# Mynd_BT.net
KiCad netlist of a schematic drawn in Altium Designer
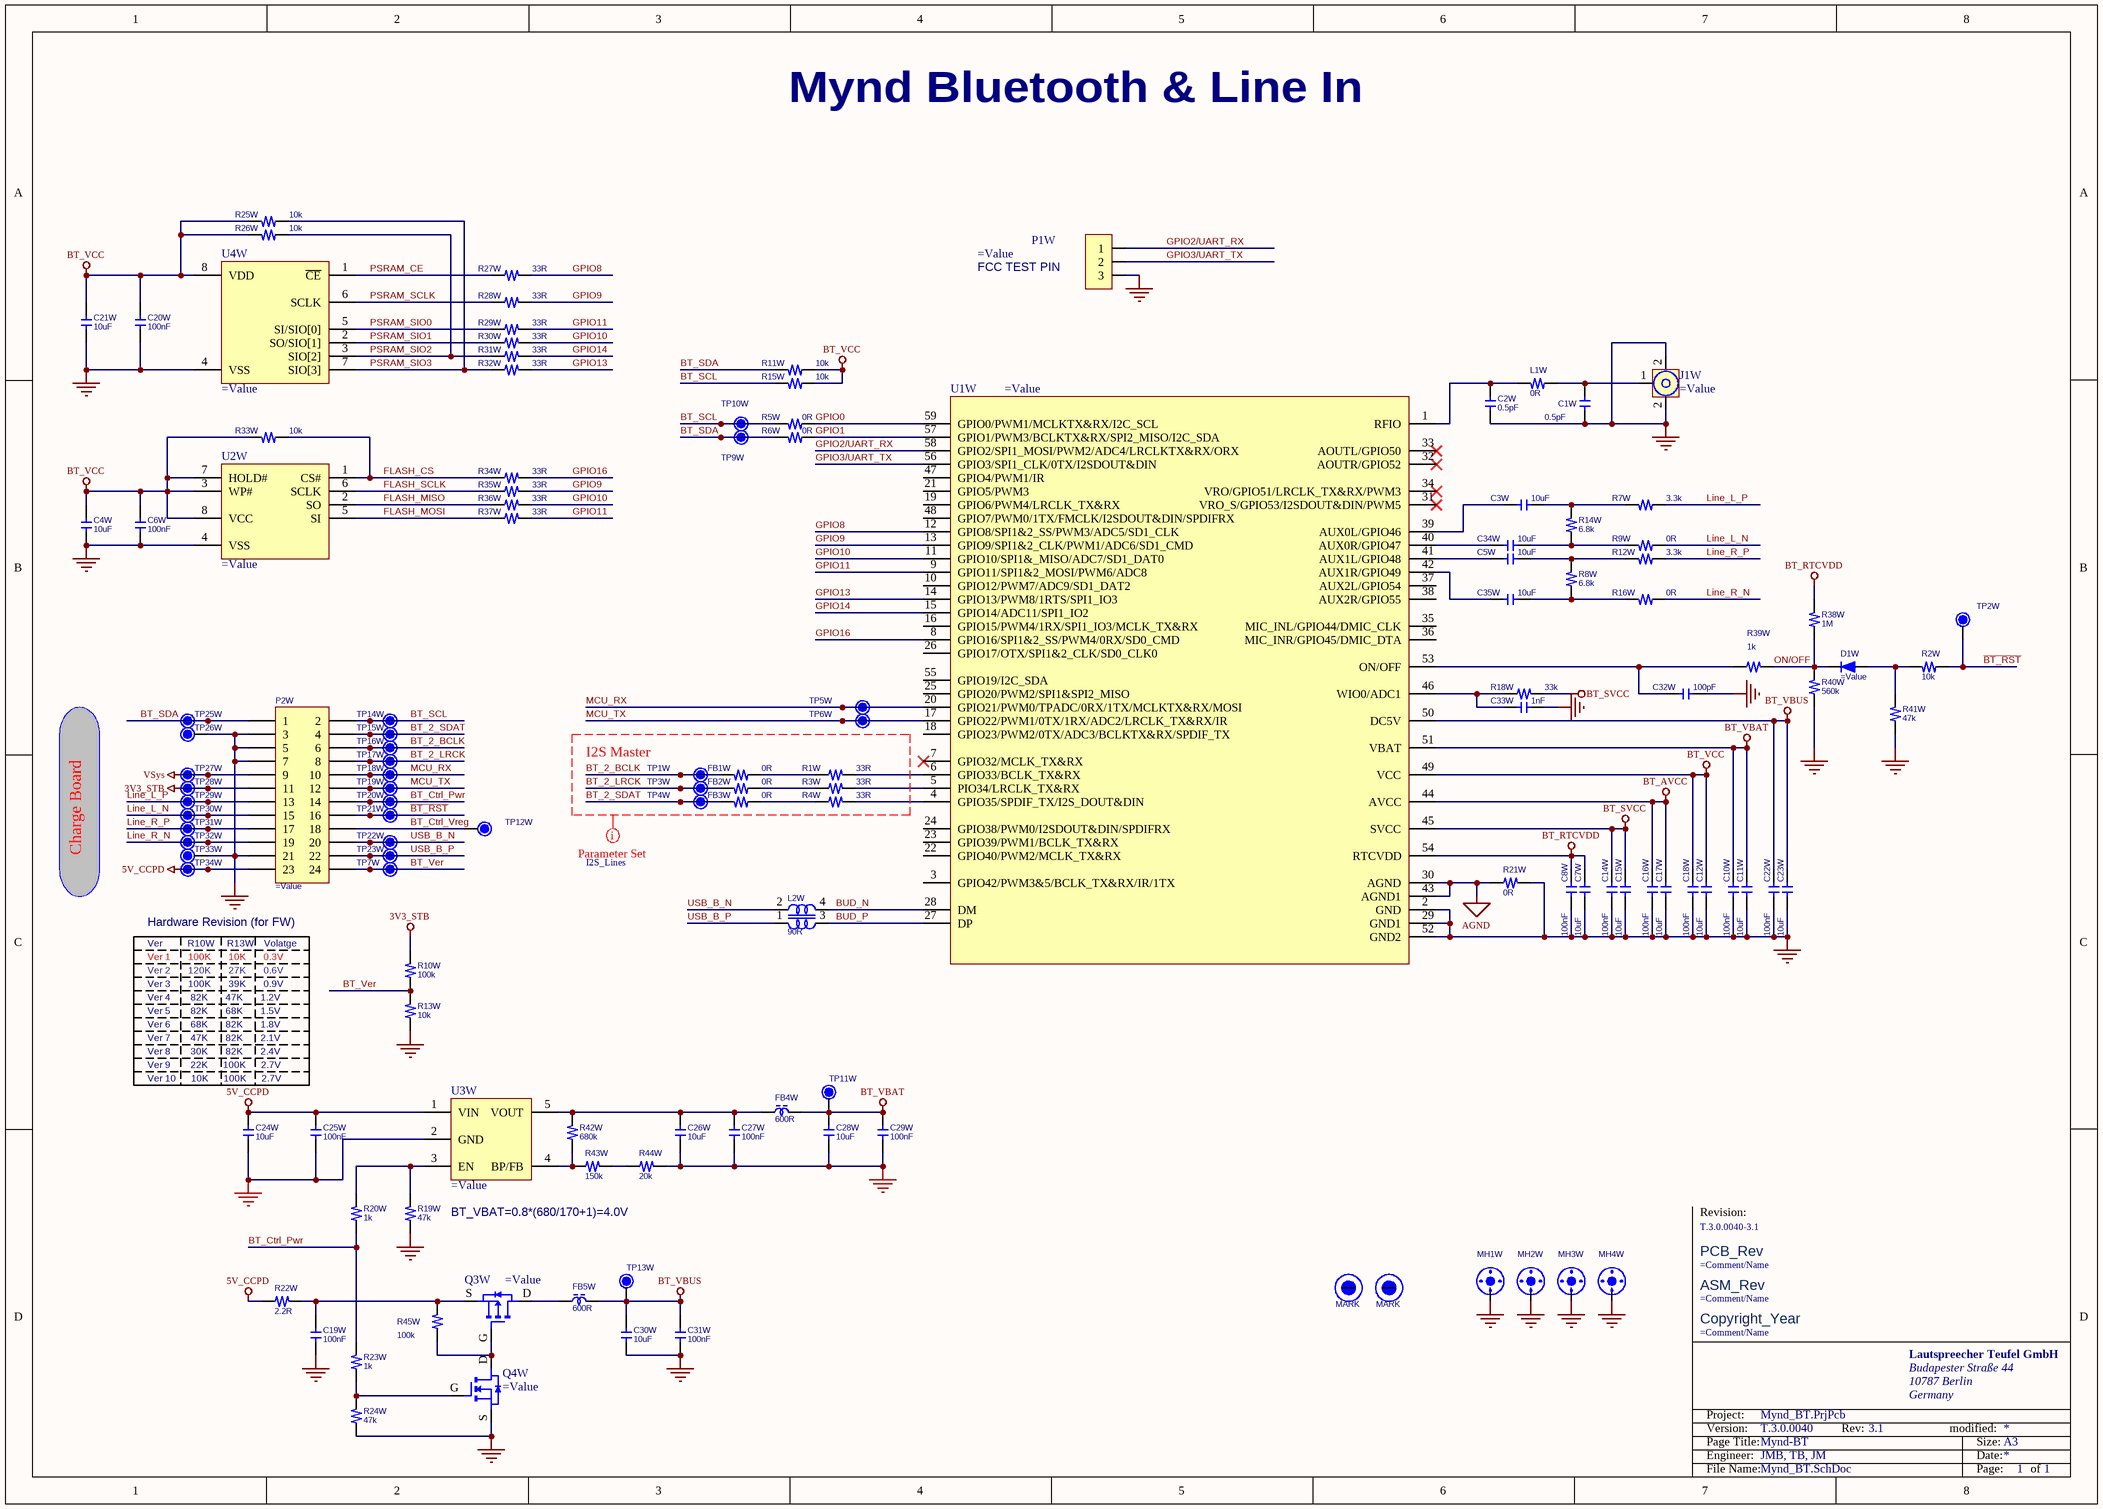
[diagram p0: Mynd_BT.SchDoc]

(export (version "E")
  (design (tool "Eeschema 10.0.6"))
  (components
    (comp (ref "C1W")
      (value "0.5pF")
      (footprint "C0402")
      (description "GP SMD M CAP 0.5pF 50V ±0.1pF 0402 NPO")
      (fields (field (name "MANUFACTURER") "Multi Sourced") (field (name "TOLERANCE") "±0.1pF"))
      (libsource (lib "altium-import") (part "root_3_mirrored_CAP1_"))
    )
    (comp (ref "C2W")
      (value "0.5pF")
      (footprint "C0402")
      (description "GP SMD M CAP 0.5pF 50V ±0.1pF 0402 NPO")
      (fields (field (name "MANUFACTURER") "Multi Sourced") (field (name "TOLERANCE") "±0.1pF"))
      (libsource (lib "altium-import") (part "root_3_mirrored_CAP1_"))
    )
    (comp (ref "C3W")
      (value "10uF")
      (footprint "C0805_145")
      (description "PSHF SMD M CAP 10uF 16V ±10% 0805 X7R")
      (fields (field (name "MANUFACTURER") "Multi Sourced") (field (name "TOLERANCE") "±10% 0805"))
      (libsource (lib "altium-import") (part "root_0_CAP1_"))
    )
    (comp (ref "C4W")
      (value "10uF")
      (footprint "C0805_145")
      (description "PSHF SMD M CAP 10uF 16V ±10% 0805 X7R")
      (fields (field (name "MANUFACTURER") "Multi Sourced") (field (name "TOLERANCE") "±10% 0805"))
      (libsource (lib "altium-import") (part "root_1_P-001-0158-27_"))
    )
    (comp (ref "C5W")
      (value "10uF")
      (footprint "C0805_145")
      (description "PSHF SMD M CAP 10uF 16V ±10% 0805 X7R")
      (fields (field (name "MANUFACTURER") "Multi Sourced") (field (name "TOLERANCE") "±10% 0805"))
      (libsource (lib "altium-import") (part "root_0_CAP1_"))
    )
    (comp (ref "C6W")
      (value "100nF")
      (footprint "C0603X100")
      (description "PSHF SMD M CAP 100nF 16V ±10%  0603 X7R")
      (fields (field (name "MANUFACTURER") "Multi Sourced") (field (name "TOLERANCE") "±10%"))
      (libsource (lib "altium-import") (part "root_1_CAP1_"))
    )
    (comp (ref "C7W")
      (value "10uF")
      (footprint "C0805_145")
      (description "PSHF SMD M CAP 10uF 16V ±10% 0805 X7R")
      (fields (field (name "MANUFACTURER") "Multi Sourced") (field (name "TOLERANCE") "±10% 0805"))
      (libsource (lib "altium-import") (part "root_3_CAP1_"))
    )
    (comp (ref "C8W")
      (value "100nF")
      (footprint "C0603X100")
      (description "PSHF SMD M CAP 100nF 16V ±10%  0603 X7R")
      (fields (field (name "MANUFACTURER") "Multi Sourced") (field (name "TOLERANCE") "±10%"))
      (libsource (lib "altium-import") (part "root_3_CAP1_"))
    )
    (comp (ref "C10W")
      (value "100nF")
      (footprint "C0603X100")
      (description "PSHF SMD M CAP 100nF 16V ±10%  0603 X7R")
      (fields (field (name "MANUFACTURER") "Multi Sourced") (field (name "TOLERANCE") "±10%"))
      (libsource (lib "altium-import") (part "root_1_CAP1_"))
    )
    (comp (ref "C11W")
      (value "10uF")
      (footprint "C0805_145")
      (description "PSHF SMD M CAP 10uF 16V ±10% 0805 X7R")
      (fields (field (name "MANUFACTURER") "Multi Sourced") (field (name "TOLERANCE") "±10% 0805"))
      (libsource (lib "altium-import") (part "root_1_P-001-0158-27_"))
    )
    (comp (ref "C12W")
      (value "10uF")
      (footprint "C0805_145")
      (description "PSHF SMD M CAP 10uF 16V ±10% 0805 X7R")
      (fields (field (name "MANUFACTURER") "Multi Sourced") (field (name "TOLERANCE") "±10% 0805"))
      (libsource (lib "altium-import") (part "root_1_CAP1_"))
    )
    (comp (ref "C14W")
      (value "100nF")
      (footprint "C0603X100")
      (description "PSHF SMD M CAP 100nF 16V ±10%  0603 X7R")
      (fields (field (name "MANUFACTURER") "Multi Sourced") (field (name "TOLERANCE") "±10%"))
      (libsource (lib "altium-import") (part "root_3_CAP1_"))
    )
    (comp (ref "C15W")
      (value "10uF")
      (footprint "C0805_145")
      (description "PSHF SMD M CAP 10uF 16V ±10% 0805 X7R")
      (fields (field (name "MANUFACTURER") "Multi Sourced") (field (name "TOLERANCE") "±10% 0805"))
      (libsource (lib "altium-import") (part "root_1_CAP1_"))
    )
    (comp (ref "C16W")
      (value "100nF")
      (footprint "C0603X100")
      (description "PSHF SMD M CAP 100nF 16V ±10%  0603 X7R")
      (fields (field (name "MANUFACTURER") "Multi Sourced") (field (name "TOLERANCE") "±10%"))
      (libsource (lib "altium-import") (part "root_3_CAP1_"))
    )
    (comp (ref "C17W")
      (value "10uF")
      (footprint "C0805_145")
      (description "PSHF SMD M CAP 10uF 16V ±10% 0805 X7R")
      (fields (field (name "MANUFACTURER") "Multi Sourced") (field (name "TOLERANCE") "±10% 0805"))
      (libsource (lib "altium-import") (part "root_1_CAP1_"))
    )
    (comp (ref "C18W")
      (value "100nF")
      (footprint "C0603X100")
      (description "PSHF SMD M CAP 100nF 16V ±10%  0603 X7R")
      (fields (field (name "MANUFACTURER") "Multi Sourced") (field (name "TOLERANCE") "±10%"))
      (libsource (lib "altium-import") (part "root_1_CAP1_"))
    )
    (comp (ref "C19W")
      (value "100nF")
      (footprint "C0603X100")
      (description "PSHF SMD M CAP 100nF 16V ±10%  0603 X7R")
      (fields (field (name "MANUFACTURER") "Multi Sourced") (field (name "TOLERANCE") "±10%"))
      (libsource (lib "altium-import") (part "root_3_CAP1_"))
    )
    (comp (ref "C20W")
      (value "100nF")
      (footprint "C0603X100")
      (description "PSHF SMD M CAP 100nF 16V ±10%  0603 X7R")
      (fields (field (name "MANUFACTURER") "Multi Sourced") (field (name "TOLERANCE") "±10%"))
      (libsource (lib "altium-import") (part "root_3_CAP1_"))
    )
    (comp (ref "C21W")
      (value "10uF")
      (footprint "C0805_145")
      (description "PSHF SMD M CAP 10uF 16V ±10% 0805 X7R")
      (fields (field (name "MANUFACTURER") "Multi Sourced") (field (name "TOLERANCE") "±10% 0805"))
      (libsource (lib "altium-import") (part "root_3_P-001-0158-27_"))
    )
    (comp (ref "C22W")
      (value "100nF")
      (footprint "C0603X100")
      (description "PSHF SMD M CAP 100nF 16V ±10%  0603 X7R")
      (fields (field (name "MANUFACTURER") "Multi Sourced") (field (name "TOLERANCE") "±10%"))
      (libsource (lib "altium-import") (part "root_3_P-001-0038-26_"))
    )
    (comp (ref "C23W")
      (value "10uF")
      (footprint "C0805_145")
      (description "PSHF SMD M CAP 10uF 16V ±10% 0805 X7R")
      (fields (field (name "MANUFACTURER") "Multi Sourced") (field (name "TOLERANCE") "±10% 0805"))
      (libsource (lib "altium-import") (part "root_3_CAP1_"))
    )
    (comp (ref "C24W")
      (value "10uF")
      (footprint "C0805_145")
      (description "PSHF SMD M CAP 10uF 16V ±10% 0805 0805 X5R")
      (fields (field (name "TOLERANCE") "±10% 0805") (field (name "MANUFACTURER") "Multi Sourced"))
      (libsource (lib "altium-import") (part "root_3_CAP1_"))
    )
    (comp (ref "C25W")
      (value "100nF")
      (footprint "C0603X100")
      (description "PSHF SMD M CAP 100nF 50V ±10% 0603 X7R")
      (fields (field (name "MANUFACTURER") "Multi Sourced") (field (name "PART_NUMBER") "Generic"))
      (libsource (lib "altium-import") (part "root_1_CAP1_"))
    )
    (comp (ref "C26W")
      (value "10uF")
      (footprint "C0805_145")
      (description "PSHF SMD M CAP 10uF 16V ±10% 0805 0805 X5R")
      (fields (field (name "TOLERANCE") "±10% 0805") (field (name "MANUFACTURER") "Multi Sourced"))
      (libsource (lib "altium-import") (part "root_3_CAP1_"))
    )
    (comp (ref "C27W")
      (value "100nF")
      (footprint "C0603X100")
      (description "PSHF SMD M CAP 100nF 16V ±10%  0603 X7R")
      (fields (field (name "MANUFACTURER") "Multi Sourced") (field (name "PART_NUMBER") "Generic"))
      (libsource (lib "altium-import") (part "root_1_CAP1_"))
    )
    (comp (ref "C28W")
      (value "10uF")
      (footprint "C0805_145")
      (description "PSHF SMD M CAP 10uF 16V ±10% 0805 0805 X5R")
      (fields (field (name "TOLERANCE") "±10% 0805") (field (name "MANUFACTURER") "Multi Sourced"))
      (libsource (lib "altium-import") (part "root_3_CAP1_"))
    )
    (comp (ref "C29W")
      (value "100nF")
      (footprint "C0603X100")
      (description "PSHF SMD M CAP 100nF 16V ±10%  0603 X7R")
      (fields (field (name "MANUFACTURER") "Multi Sourced") (field (name "PART_NUMBER") "Generic"))
      (libsource (lib "altium-import") (part "root_1_CAP1_"))
    )
    (comp (ref "C30W")
      (value "10uF")
      (footprint "C0805_145")
      (description "PSHF SMD M CAP 10uF 16V ±10% 0805 X7R")
      (fields (field (name "MANUFACTURER") "Multi Sourced") (field (name "TOLERANCE") "±10% 0805"))
      (libsource (lib "altium-import") (part "root_1_P-001-0158-27_"))
    )
    (comp (ref "C31W")
      (value "100nF")
      (footprint "C0603X100")
      (description "PSHF SMD M CAP 100nF 16V ±10%  0603 X7R")
      (fields (field (name "MANUFACTURER") "Multi Sourced") (field (name "TOLERANCE") "±10%"))
      (libsource (lib "altium-import") (part "root_1_CAP1_"))
    )
    (comp (ref "C32W")
      (value "100pF")
      (footprint "C0603X80")
      (description "PSHF SMD M CAP 100pF 50V ±10% 0603 X7R")
      (fields (field (name "MANUFACTURER") "Multi Sourced") (field (name "PART_NUMBER") "Generic"))
      (libsource (lib "altium-import") (part "root_2_CAP1_"))
    )
    (comp (ref "C33W")
      (value "1nF")
      (footprint "C0603X100")
      (description "PSHF SMD M CAP 1nF 50V ±10% 0603 X7R")
      (fields (field (name "MANUFACTURER") "Multi Sourced") (field (name "PART_NUMBER") "Generic"))
      (libsource (lib "altium-import") (part "root_2_CAP1_"))
    )
    (comp (ref "C34W")
      (value "10uF")
      (footprint "C0805_145")
      (description "PSHF SMD M CAP 10uF 16V ±10% 0805 X7R")
      (fields (field (name "MANUFACTURER") "Multi Sourced") (field (name "TOLERANCE") "±10% 0805"))
      (libsource (lib "altium-import") (part "root_0_CAP1_"))
    )
    (comp (ref "C35W")
      (value "10uF")
      (footprint "C0805_145")
      (description "PSHF SMD M CAP 10uF 16V ±10% 0805 X7R")
      (fields (field (name "MANUFACTURER") "Multi Sourced") (field (name "TOLERANCE") "±10% 0805"))
      (libsource (lib "altium-import") (part "root_0_CAP1_"))
    )
    (comp (ref "D1W")
      (value "~")
      (footprint "SOD-323")
      (description "PS SMD DIODE 2P 100V SOD323 1N4148 CJ")
      (fields (field (name "MANUFACTURER") "[CJ]") (field (name "PART_NUMBER") "1N4148"))
      (libsource (lib "altium-import") (part "root_2_DIODE_SWITCHING1_"))
    )
    (comp (ref "FB1W")
      (value "0R")
      (footprint "R0603")
      (description "GPHF SMD RES. 0OHM 1/10W 5% 0603")
      (fields (field (name "MANUFACTURER") "Multi Sourced") (field (name "TOLERANCE") "5%"))
      (libsource (lib "altium-import") (part "root_0_RES1_"))
    )
    (comp (ref "FB2W")
      (value "0R")
      (footprint "R0603")
      (description "GPHF SMD RES. 0OHM 1/10W 5% 0603")
      (fields (field (name "MANUFACTURER") "Multi Sourced") (field (name "TOLERANCE") "5%"))
      (libsource (lib "altium-import") (part "root_0_RES1_"))
    )
    (comp (ref "FB3W")
      (value "0R")
      (footprint "R0603")
      (description "GPHF SMD RES. 0OHM 1/10W 5% 0603")
      (fields (field (name "MANUFACTURER") "Multi Sourced") (field (name "TOLERANCE") "5%"))
      (libsource (lib "altium-import") (part "root_0_RES1_"))
    )
    (comp (ref "FB4W")
      (value "600R")
      (footprint "L0603")
      (description "PS SMD FERRITE BEAD 600OHM 25% 0603")
      (fields (field (name "MANUFACTURER") "[TSA]") (field (name "TOLERANCE") "1:25%"))
      (libsource (lib "altium-import") (part "root_0_Bead1_"))
    )
    (comp (ref "FB5W")
      (value "600R")
      (footprint "L0603")
      (description "PS SMD FERRITE BEAD 600OHM 25% 0603")
      (fields (field (name "MANUFACTURER") "[TSA]") (field (name "TOLERANCE") "1:25%"))
      (libsource (lib "altium-import") (part "root_0_Bead1_"))
    )
    (comp (ref "J1W")
      (value "~")
      (footprint "I-PEX MHF")
      (description "SMD ANTENNA JACK 2P FEMALE")
      (fields (field (name "MANUFACTURER") "[SONGCHENG]") (field (name "PART_NUMBER") "9181-000030"))
      (libsource (lib "altium-import") (part "root_2_COA_CON1_"))
    )
    (comp (ref "L1W")
      (value "0R")
      (footprint "R0402")
      (description "GPHF SMD RES. 0OHM 1/16W 5% 0402")
      (fields (field (name "MANUFACTURER") "Multi Sourced") (field (name "TOLERANCE") "5%"))
      (libsource (lib "altium-import") (part "root_0_mirrored_RES1_"))
    )
    (comp (ref "L2W")
      (value "90R")
      (footprint "COM_CHOKE_SMD_ICMF062P")
      (description "FILTER ICMF062P900MFR 100MHz 4P 90ohm")
      (fields (field (name "MANUFACTURER") "TSA") (field (name "PART_NUMBER") "ICMF062P900MFR"))
      (libsource (lib "altium-import") (part "root_2_mirrored_INDUCTOR_CM_4_"))
    )
    (comp (ref "MH1W")
      (value "SCREW_HOLE")
      (footprint "SCREW_D32")
      (description "SCREW_HOLE D3.2mm")
      (libsource (lib "altium-import") (part "root_1_SCREW_HOLE_"))
    )
    (comp (ref "MH2W")
      (value "SCREW_HOLE")
      (footprint "SCREW_D32")
      (description "SCREW_HOLE D3.2mm")
      (libsource (lib "altium-import") (part "root_1_SCREW_HOLE_"))
    )
    (comp (ref "MH3W")
      (value "SCREW_HOLE")
      (footprint "SCREW_D32")
      (description "SCREW_HOLE D3.2mm")
      (libsource (lib "altium-import") (part "root_1_SCREW_HOLE_"))
    )
    (comp (ref "MH4W")
      (value "SCREW_HOLE")
      (footprint "SCREW_D32")
      (description "SCREW_HOLE D3.2mm")
      (libsource (lib "altium-import") (part "root_1_SCREW_HOLE_"))
    )
    (comp (ref "MK1W")
      (value "MARK")
      (footprint "MARK")
      (description "MARK DOT")
      (libsource (lib "altium-import") (part "root_0_MARK_"))
    )
    (comp (ref "MK2W")
      (value "MARK")
      (footprint "MARK")
      (description "MARK DOT")
      (libsource (lib "altium-import") (part "root_0_MARK_"))
    )
    (comp (ref "P1W")
      (value "~")
      (footprint "Pin_Header_SMD_S_T_254_3P")
      (description "GP HEADER PIN 3P P=2.54mm 90° GOLD")
      (fields (field (name "PART_NUMBER") "Header 3P PITCH=2.54mm SMT"))
      (libsource (lib "altium-import") (part "root_0_CON 3P_"))
    )
    (comp (ref "P2W")
      (value "~")
      (footprint "Pin_Header_SMD_2X12_254")
      (description "SMD BTB CONNECTOR 24P P2.54mm GOLD")
      (fields
        (field (name "MANUFACTURER") "MINGHENG")
        (field (name "PART_NUMBER") "Connector 2 x 12P 2.54mm SMT")
      )
      (libsource (lib "altium-import") (part "root_0_CON 2x12P_"))
    )
    (comp (ref "Q3W")
      (value "~")
      (footprint "SOT23-GSD")
      (description "GS SMD FET 3P -30V SOT-23 CJ3401 CJ")
      (fields (field (name "MANUFACTURER") "[CJ]") (field (name "PART_NUMBER") "CJ3401"))
      (libsource (lib "altium-import") (part "root_1_mirrored_P-MOS1_"))
    )
    (comp (ref "Q4W")
      (value "~")
      (footprint "SOT23-GSD")
      (description "GP SMD FET 3P SOT23 2N7002K CTE")
      (fields (field (name "MANUFACTURER") "CTE") (field (name "PART_NUMBER") "2N7002K"))
      (libsource (lib "altium-import") (part "root_0_N-MOS1_"))
    )
    (comp (ref "R1W")
      (value "33R")
      (footprint "R0603")
      (description "PS SMD RES. 33OHM 1/10W 5% 0603")
      (fields (field (name "TOLERANCE") "5%") (field (name "MANUFACTURER") "Multi Sourced"))
      (libsource (lib "altium-import") (part "root_2_RES1_"))
    )
    (comp (ref "R2W")
      (value "10k")
      (footprint "R0603")
      (description "PS SMD RES. 10KOHM 1/10W 1% 0603")
      (fields (field (name "TOLERANCE") "1%") (field (name "MANUFACTURER") "Multi Sourced"))
      (libsource (lib "altium-import") (part "root_0_RES1_"))
    )
    (comp (ref "R3W")
      (value "33R")
      (footprint "R0603")
      (description "PS SMD RES. 33OHM 1/10W 5% 0603")
      (fields (field (name "TOLERANCE") "5%") (field (name "MANUFACTURER") "Multi Sourced"))
      (libsource (lib "altium-import") (part "root_2_RES1_"))
    )
    (comp (ref "R4W")
      (value "33R")
      (footprint "R0603")
      (description "PS SMD RES. 33OHM 1/10W 5% 0603")
      (fields (field (name "TOLERANCE") "5%") (field (name "MANUFACTURER") "Multi Sourced"))
      (libsource (lib "altium-import") (part "root_2_RES1_"))
    )
    (comp (ref "R5W")
      (value "0R")
      (footprint "R0603")
      (description "PS SMD RES. 0OHM 1/10W 5% 0603")
      (fields (field (name "TOLERANCE") "5%") (field (name "MANUFACTURER") "Multi Sourced"))
      (libsource (lib "altium-import") (part "root_0_RES1_"))
    )
    (comp (ref "R6W")
      (value "0R")
      (footprint "R0603")
      (description "PS SMD RES. 0OHM 1/10W 5% 0603")
      (fields (field (name "TOLERANCE") "5%") (field (name "MANUFACTURER") "Multi Sourced"))
      (libsource (lib "altium-import") (part "root_0_RES1_"))
    )
    (comp (ref "R7W")
      (value "3.3k")
      (footprint "R0603")
      (description "GPHF SMD RES. 3.3KOHM 1/10W 1% 0603")
      (fields (field (name "TOLERANCE") "1%") (field (name "MANUFACTURER") "Multi Sourced"))
      (libsource (lib "altium-import") (part "root_0_RES1_"))
    )
    (comp (ref "R8W")
      (value "6.8k")
      (footprint "R0603")
      (description "PS SMD RES. 6.8KOHM 1/10W 1% 0603")
      (fields (field (name "TOLERANCE") "1%") (field (name "MANUFACTURER") "Multi Sourced"))
      (libsource (lib "altium-import") (part "root_1_mirrored_RES1_"))
    )
    (comp (ref "R9W")
      (value "0R")
      (footprint "R0603")
      (description "PS SMD RES. 0OHM 1/10W 5% 0603")
      (fields (field (name "TOLERANCE") "5%") (field (name "MANUFACTURER") "Multi Sourced"))
      (libsource (lib "altium-import") (part "root_0_RES1_"))
    )
    (comp (ref "R10W")
      (value "100k")
      (footprint "R0603")
      (description "GPHF SMD RES. 100KOHM 1/10W 1% 0603")
      (fields (field (name "TOLERANCE") "1%") (field (name "MANUFACTURER") "Multi Sourced"))
      (libsource (lib "altium-import") (part "root_3_RES1_"))
    )
    (comp (ref "R11W")
      (value "10k")
      (footprint "R0603")
      (description "PS SMD RES. 10KOHM 1/10W 1% 0603")
      (fields (field (name "TOLERANCE") "1%") (field (name "MANUFACTURER") "Multi Sourced"))
      (libsource (lib "altium-import") (part "root_0_mirrored_RES1_"))
    )
    (comp (ref "R12W")
      (value "3.3k")
      (footprint "R0603")
      (description "GPHF SMD RES. 3.3KOHM 1/10W 1% 0603")
      (fields (field (name "TOLERANCE") "1%") (field (name "MANUFACTURER") "Multi Sourced"))
      (libsource (lib "altium-import") (part "root_0_RES1_"))
    )
    (comp (ref "R13W")
      (value "10k")
      (footprint "R0603")
      (description "GPHF SMD RES. 10KOHM 1/10W 1% 0603")
      (fields (field (name "TOLERANCE") "1%") (field (name "MANUFACTURER") "Multi Sourced"))
      (libsource (lib "altium-import") (part "root_3_RES1_"))
    )
    (comp (ref "R14W")
      (value "6.8k")
      (footprint "R0603")
      (description "PS SMD RES. 6.8KOHM 1/10W 1% 0603")
      (fields (field (name "TOLERANCE") "1%") (field (name "MANUFACTURER") "Multi Sourced"))
      (libsource (lib "altium-import") (part "root_1_mirrored_RES1_"))
    )
    (comp (ref "R15W")
      (value "10k")
      (footprint "R0603")
      (description "PS SMD RES. 10KOHM 1/10W 1% 0603")
      (fields (field (name "TOLERANCE") "1%") (field (name "MANUFACTURER") "Multi Sourced"))
      (libsource (lib "altium-import") (part "root_0_mirrored_RES1_"))
    )
    (comp (ref "R16W")
      (value "0R")
      (footprint "R0603")
      (description "PS SMD RES. 0OHM 1/10W 5% 0603")
      (fields (field (name "TOLERANCE") "5%") (field (name "MANUFACTURER") "Multi Sourced"))
      (libsource (lib "altium-import") (part "root_0_RES1_"))
    )
    (comp (ref "R18W")
      (value "33k")
      (footprint "R0603")
      (description "PS SMD RES. 33KOHM 1/10W 1% 0603")
      (fields (field (name "TOLERANCE") "1%") (field (name "MANUFACTURER") "Multi Sourced"))
      (libsource (lib "altium-import") (part "root_2_RES1_"))
    )
    (comp (ref "R19W")
      (value "47k")
      (footprint "R0603")
      (description "PS SMD RES. 47KOHM 1/10W 1% 0603")
      (fields (field (name "TOLERANCE") "1%") (field (name "MANUFACTURER") "Multi Sourced"))
      (libsource (lib "altium-import") (part "root_3_RES1_"))
    )
    (comp (ref "R20W")
      (value "1k")
      (footprint "R0603")
      (description "PS SMD RES. 1KOHM 1/10W 1% 0603")
      (fields (field (name "TOLERANCE") "1%") (field (name "MANUFACTURER") "Multi Sourced"))
      (libsource (lib "altium-import") (part "root_3_RES1_"))
    )
    (comp (ref "R21W")
      (value "0R")
      (footprint "R0603")
      (description "PS SMD RES. 0OHM 1/10W 5% 0603")
      (fields (field (name "TOLERANCE") "5%") (field (name "MANUFACTURER") "Multi Sourced"))
      (libsource (lib "altium-import") (part "root_2_RES1_"))
    )
    (comp (ref "R22W")
      (value "2.2R")
      (footprint "R0805")
      (description "PS SMD RES. 2.2OHM 1/8W 5% 0805")
      (fields (field (name "TOLERANCE") "5%") (field (name "MANUFACTURER") "Multi Sourced"))
      (libsource (lib "altium-import") (part "root_2_RES1_"))
    )
    (comp (ref "R23W")
      (value "1k")
      (footprint "R0603")
      (description "PS SMD RES. 1KOHM 1/10W 1% 0603")
      (fields (field (name "TOLERANCE") "1%") (field (name "MANUFACTURER") "Multi Sourced"))
      (libsource (lib "altium-import") (part "root_3_RES1_"))
    )
    (comp (ref "R24W")
      (value "47k")
      (footprint "R0603")
      (description "PS SMD RES. 47KOHM 1/10W 1% 0603")
      (fields (field (name "TOLERANCE") "1%") (field (name "MANUFACTURER") "Multi Sourced"))
      (libsource (lib "altium-import") (part "root_3_RES1_"))
    )
    (comp (ref "R25W")
      (value "10k")
      (footprint "R0603")
      (description "PS SMD RES. 10KOHM 1/10W 1% 0603")
      (fields (field (name "TOLERANCE") "1%") (field (name "MANUFACTURER") "Multi Sourced"))
      (libsource (lib "altium-import") (part "root_0_RES1_"))
    )
    (comp (ref "R26W")
      (value "10k")
      (footprint "R0603")
      (description "PS SMD RES. 10KOHM 1/10W 1% 0603")
      (fields (field (name "TOLERANCE") "1%") (field (name "MANUFACTURER") "Multi Sourced"))
      (libsource (lib "altium-import") (part "root_0_RES1_"))
    )
    (comp (ref "R27W")
      (value "33R")
      (footprint "R0603")
      (description "PS SMD RES. 33OHM 1/10W 5% 0603")
      (fields (field (name "TOLERANCE") "5%") (field (name "MANUFACTURER") "Multi Sourced"))
      (libsource (lib "altium-import") (part "root_2_RES1_"))
    )
    (comp (ref "R28W")
      (value "33R")
      (footprint "R0603")
      (description "PS SMD RES. 33OHM 1/10W 5% 0603")
      (fields (field (name "TOLERANCE") "5%") (field (name "MANUFACTURER") "Multi Sourced"))
      (libsource (lib "altium-import") (part "root_2_RES1_"))
    )
    (comp (ref "R29W")
      (value "33R")
      (footprint "R0603")
      (description "PS SMD RES. 33OHM 1/10W 5% 0603")
      (fields (field (name "TOLERANCE") "5%") (field (name "MANUFACTURER") "Multi Sourced"))
      (libsource (lib "altium-import") (part "root_2_RES1_"))
    )
    (comp (ref "R30W")
      (value "33R")
      (footprint "R0603")
      (description "PS SMD RES. 33OHM 1/10W 5% 0603")
      (fields (field (name "TOLERANCE") "5%") (field (name "MANUFACTURER") "Multi Sourced"))
      (libsource (lib "altium-import") (part "root_2_RES1_"))
    )
    (comp (ref "R31W")
      (value "33R")
      (footprint "R0603")
      (description "PS SMD RES. 33OHM 1/10W 5% 0603")
      (fields (field (name "TOLERANCE") "5%") (field (name "MANUFACTURER") "Multi Sourced"))
      (libsource (lib "altium-import") (part "root_2_RES1_"))
    )
    (comp (ref "R32W")
      (value "33R")
      (footprint "R0603")
      (description "PS SMD RES. 33OHM 1/10W 5% 0603")
      (fields (field (name "TOLERANCE") "5%") (field (name "MANUFACTURER") "Multi Sourced"))
      (libsource (lib "altium-import") (part "root_2_RES1_"))
    )
    (comp (ref "R33W")
      (value "10k")
      (footprint "R0603")
      (description "PS SMD RES. 10KOHM 1/10W 1% 0603")
      (fields (field (name "TOLERANCE") "1%") (field (name "MANUFACTURER") "Multi Sourced"))
      (libsource (lib "altium-import") (part "root_0_RES1_"))
    )
    (comp (ref "R34W")
      (value "33R")
      (footprint "R0603")
      (description "PS SMD RES. 33OHM 1/10W 5% 0603")
      (fields (field (name "TOLERANCE") "5%") (field (name "MANUFACTURER") "Multi Sourced"))
      (libsource (lib "altium-import") (part "root_2_RES1_"))
    )
    (comp (ref "R35W")
      (value "33R")
      (footprint "R0603")
      (description "PS SMD RES. 33OHM 1/10W 5% 0603")
      (fields (field (name "TOLERANCE") "5%") (field (name "MANUFACTURER") "Multi Sourced"))
      (libsource (lib "altium-import") (part "root_2_RES1_"))
    )
    (comp (ref "R36W")
      (value "33R")
      (footprint "R0603")
      (description "PS SMD RES. 33OHM 1/10W 5% 0603")
      (fields (field (name "TOLERANCE") "5%") (field (name "MANUFACTURER") "Multi Sourced"))
      (libsource (lib "altium-import") (part "root_2_RES1_"))
    )
    (comp (ref "R37W")
      (value "33R")
      (footprint "R0603")
      (description "PS SMD RES. 33OHM 1/10W 5% 0603")
      (fields (field (name "TOLERANCE") "5%") (field (name "MANUFACTURER") "Multi Sourced"))
      (libsource (lib "altium-import") (part "root_2_RES1_"))
    )
    (comp (ref "R38W")
      (value "1M")
      (footprint "R0603")
      (description "PS SMD RES. 1MOHM 1/10W 1% 0603")
      (fields (field (name "TOLERANCE") "1%") (field (name "MANUFACTURER") "Multi Sourced"))
      (libsource (lib "altium-import") (part "root_3_RES1_"))
    )
    (comp (ref "R39W")
      (value "1k")
      (footprint "R0603")
      (description "PS SMD RES. 1KOHM 1/10W 1% 0603")
      (fields (field (name "TOLERANCE") "1%") (field (name "MANUFACTURER") "Multi Sourced"))
      (libsource (lib "altium-import") (part "root_2_RES1_"))
    )
    (comp (ref "R40W")
      (value "560k")
      (footprint "R0603")
      (description "PS SMD RES. 560KOHM 1/10W 5% 0603")
      (fields (field (name "TOLERANCE") "5%") (field (name "MANUFACTURER") "Multi Sourced"))
      (libsource (lib "altium-import") (part "root_3_RES1_"))
    )
    (comp (ref "R41W")
      (value "47k")
      (footprint "R0603")
      (description "PS SMD RES. 47KOHM 1/10W 1% 0603")
      (fields (field (name "TOLERANCE") "1%") (field (name "MANUFACTURER") "Multi Sourced"))
      (libsource (lib "altium-import") (part "root_3_RES1_"))
    )
    (comp (ref "R42W")
      (value "680k")
      (footprint "R0603")
      (description "PS SMD RES. 680KOHM 1/10W 5% 0603")
      (fields (field (name "MANUFACTURER") "Multi Sourced") (field (name "PART_NUMBER") "Generic"))
      (libsource (lib "altium-import") (part "root_3_RES1_"))
    )
    (comp (ref "R43W")
      (value "150k")
      (footprint "R0603")
      (description "PS SMD RES. 150KOHM 1/10W 1% 0603")
      (fields (field (name "TOLERANCE") "1%") (field (name "PART_NUMBER") "Generic"))
      (libsource (lib "altium-import") (part "root_2_RES1_"))
    )
    (comp (ref "R44W")
      (value "20k")
      (footprint "R0603")
      (description "PS SMD RES. 20KOHM 1/10W 1% 0603")
      (fields (field (name "TOLERANCE") "1%") (field (name "PART_NUMBER") "Generic"))
      (libsource (lib "altium-import") (part "root_2_RES1_"))
    )
    (comp (ref "R45W")
      (value "100k")
      (footprint "R0402")
      (description "GPHF SMD RES. 100KOHM 1/16W 1% 0402")
      (fields (field (name "TOLERANCE") "1%") (field (name "MANUFACTURER") "Multi Sourced"))
      (libsource (lib "altium-import") (part "root_3_RES1_"))
    )
    (comp (ref "Teufel_ASM_Label1W")
      (value "~")
      (footprint "Teufel_ASM_Rev")
      (description "Teufel_ASM_Rev")
      (libsource (lib "altium-import") (part "root_0_Teufel_ASM_Label_"))
    )
    (comp (ref "Teufel_Copyright1W")
      (value "~")
      (footprint "TEUFEL_COPYRIGHT")
      (description "Teufel_Copyright_Year")
      (libsource (lib "altium-import") (part "root_0_Teufel_Copyright_"))
    )
    (comp (ref "Teufel_PCB_Label1W")
      (value "~")
      (footprint "Teufel_PCB_Rev")
      (description "Teufel_PCB_Label")
      (libsource (lib "altium-import") (part "root_0_Teufel_PCB_Label_"))
    )
    (comp (ref "Teufel_PCB_Logo1W")
      (value "-3.1")
      (footprint "Teufel_NoLogo")
      (description "Teufel PCB NoLogo")
      (libsource (lib "altium-import") (part "root_0_Teufel NoLogo_"))
    )
    (comp (ref "TP1W")
      (value "TP12")
      (footprint "TP120")
      (description "Test Point")
      (libsource (lib "altium-import") (part "root_0_TP_"))
    )
    (comp (ref "TP2W")
      (value "TP12")
      (footprint "TP120")
      (description "Test Point")
      (libsource (lib "altium-import") (part "root_1_TP_"))
    )
    (comp (ref "TP3W")
      (value "TP12")
      (footprint "TP120")
      (description "Test Point")
      (libsource (lib "altium-import") (part "root_0_TP_"))
    )
    (comp (ref "TP4W")
      (value "TP12")
      (footprint "TP120")
      (description "Test Point")
      (libsource (lib "altium-import") (part "root_0_TP_"))
    )
    (comp (ref "TP5W")
      (value "TP12")
      (footprint "TP120")
      (description "Test Point")
      (libsource (lib "altium-import") (part "root_0_TP_"))
    )
    (comp (ref "TP6W")
      (value "TP12")
      (footprint "TP120")
      (description "Test Point")
      (libsource (lib "altium-import") (part "root_0_TP_"))
    )
    (comp (ref "TP7W")
      (value "TP12")
      (footprint "TP120")
      (description "Test Point")
      (libsource (lib "altium-import") (part "root_0_TP_"))
    )
    (comp (ref "TP9W")
      (value "TP12")
      (footprint "TP120")
      (description "Test Point")
      (libsource (lib "altium-import") (part "root_0_TP_"))
    )
    (comp (ref "TP10W")
      (value "TP12")
      (footprint "TP120")
      (description "Test Point")
      (libsource (lib "altium-import") (part "root_0_TP_"))
    )
    (comp (ref "TP11W")
      (value "TP06")
      (footprint "TP060")
      (description "Test Point")
      (libsource (lib "altium-import") (part "root_1_TP_"))
    )
    (comp (ref "TP12W")
      (value "TP12")
      (footprint "TP120")
      (description "Test Point")
      (libsource (lib "altium-import") (part "root_0_TP_"))
    )
    (comp (ref "TP13W")
      (value "TP06")
      (footprint "TP060")
      (description "Test Point")
      (libsource (lib "altium-import") (part "root_1_TP_"))
    )
    (comp (ref "TP14W")
      (value "TP12")
      (footprint "TP120")
      (description "Test Point")
      (libsource (lib "altium-import") (part "root_0_TP_"))
    )
    (comp (ref "TP15W")
      (value "TP12")
      (footprint "TP120")
      (description "Test Point")
      (libsource (lib "altium-import") (part "root_0_TP_"))
    )
    (comp (ref "TP16W")
      (value "TP12")
      (footprint "TP120")
      (description "Test Point")
      (libsource (lib "altium-import") (part "root_0_TP_"))
    )
    (comp (ref "TP17W")
      (value "TP12")
      (footprint "TP120")
      (description "Test Point")
      (libsource (lib "altium-import") (part "root_0_TP_"))
    )
    (comp (ref "TP18W")
      (value "TP12")
      (footprint "TP120")
      (description "Test Point")
      (libsource (lib "altium-import") (part "root_0_TP_"))
    )
    (comp (ref "TP19W")
      (value "TP12")
      (footprint "TP120")
      (description "Test Point")
      (libsource (lib "altium-import") (part "root_0_TP_"))
    )
    (comp (ref "TP20W")
      (value "TP12")
      (footprint "TP120")
      (description "Test Point")
      (libsource (lib "altium-import") (part "root_0_TP_"))
    )
    (comp (ref "TP21W")
      (value "TP12")
      (footprint "TP120")
      (description "Test Point")
      (libsource (lib "altium-import") (part "root_0_TP_"))
    )
    (comp (ref "TP22W")
      (value "TP12")
      (footprint "TP120")
      (description "Test Point")
      (libsource (lib "altium-import") (part "root_0_TP_"))
    )
    (comp (ref "TP23W")
      (value "TP12")
      (footprint "TP120")
      (description "Test Point")
      (libsource (lib "altium-import") (part "root_0_TP_"))
    )
    (comp (ref "TP25W")
      (value "TP12")
      (footprint "TP120")
      (description "Test Point")
      (libsource (lib "altium-import") (part "root_0_mirrored_TP_"))
    )
    (comp (ref "TP26W")
      (value "TP12")
      (footprint "TP120")
      (description "Test Point")
      (libsource (lib "altium-import") (part "root_0_mirrored_TP_"))
    )
    (comp (ref "TP27W")
      (value "TP12")
      (footprint "TP120")
      (description "Test Point")
      (libsource (lib "altium-import") (part "root_0_mirrored_TP_"))
    )
    (comp (ref "TP28W")
      (value "TP12")
      (footprint "TP120")
      (description "Test Point")
      (libsource (lib "altium-import") (part "root_0_mirrored_TP_"))
    )
    (comp (ref "TP29W")
      (value "TP12")
      (footprint "TP120")
      (description "Test Point")
      (libsource (lib "altium-import") (part "root_0_mirrored_TP_"))
    )
    (comp (ref "TP30W")
      (value "TP12")
      (footprint "TP120")
      (description "Test Point")
      (libsource (lib "altium-import") (part "root_0_mirrored_TP_"))
    )
    (comp (ref "TP31W")
      (value "TP12")
      (footprint "TP120")
      (description "Test Point")
      (libsource (lib "altium-import") (part "root_0_mirrored_TP_"))
    )
    (comp (ref "TP32W")
      (value "TP12")
      (footprint "TP120")
      (description "Test Point")
      (libsource (lib "altium-import") (part "root_0_mirrored_TP_"))
    )
    (comp (ref "TP33W")
      (value "TP12")
      (footprint "TP120")
      (description "Test Point")
      (libsource (lib "altium-import") (part "root_0_mirrored_TP_"))
    )
    (comp (ref "TP34W")
      (value "TP12")
      (footprint "TP120")
      (description "Test Point")
      (libsource (lib "altium-import") (part "root_0_mirrored_TP_"))
    )
    (comp (ref "U1W")
      (value "~")
      (footprint "BT_59P_L260XW150XH26_P105")
      (description "BT MODULE 59P WB-2835P WORLDELITE")
      (fields (field (name "MANUFACTURER") "WORLDELITE") (field (name "PART_NUMBER") "WB-2835P"))
      (libsource (lib "altium-import") (part "root_0_BT_WB_2835P_"))
    )
    (comp (ref "U2W")
      (value "~")
      (footprint "SO_8_200")
      (description "PS SMD IC 8P SOP EN25QH64A EON")
      (fields (field (name "PART_NUMBER") "RCI025064-B000"))
      (libsource (lib "altium-import") (part "root_0_mirrored_SERIAL FLASH 8Pin_"))
    )
    (comp (ref "U3W")
      (value "~")
      (footprint "SOT23-5")
      (description "GP SMD IC 5P SC70 SGM2036-ADJYN5G/TR SGMICRO")
      (fields (field (name "MANUFACTURER") "[SGMICRO]") (field (name "PART_NUMBER") "SGM2036-ADJYN5G/TR"))
      (libsource (lib "altium-import") (part "root_0_SGM2036_YN5G_"))
    )
    (comp (ref "U4W")
      (value "~")
      (footprint "SO-8")
      (description "QSPI PSRAM")
      (fields (field (name "PART_NUMBER") "APS6404L-3SQN") (field (name "MANUFACTURER") "APS"))
      (libsource (lib "altium-import") (part "root_0_APS6404L-3SQN_"))
    )
  )
  (nets
    (net (code "1") (name "/BT_2_BCLK") (class "Default")
      (node (ref "FB1W") (pin "1") (pinfunction "1_1") (pintype "passive"))
      (node (ref "P2W") (pin "6") (pinfunction "6_6") (pintype "passive"))
      (node (ref "TP16W") (pin "1") (pinfunction "1_1") (pintype "passive"))
      (node (ref "TP1W") (pin "1") (pinfunction "1_1") (pintype "passive"))
    )
    (net (code "2") (name "/BT_2_LRCK") (class "Default")
      (node (ref "FB2W") (pin "1") (pinfunction "1_1") (pintype "passive"))
      (node (ref "P2W") (pin "8") (pinfunction "8_8") (pintype "passive"))
      (node (ref "TP17W") (pin "1") (pinfunction "1_1") (pintype "passive"))
      (node (ref "TP3W") (pin "1") (pinfunction "1_1") (pintype "passive"))
    )
    (net (code "3") (name "/BT_2_SDAT") (class "Default")
      (node (ref "FB3W") (pin "1") (pinfunction "1_1") (pintype "passive"))
      (node (ref "P2W") (pin "4") (pinfunction "4_4") (pintype "passive"))
      (node (ref "TP15W") (pin "1") (pinfunction "1_1") (pintype "passive"))
      (node (ref "TP4W") (pin "1") (pinfunction "1_1") (pintype "passive"))
    )
    (net (code "4") (name "/BT_Ctrl_Pwr") (class "Default")
      (node (ref "P2W") (pin "14") (pinfunction "14_14") (pintype "passive"))
      (node (ref "R20W") (pin "2") (pinfunction "2_2") (pintype "passive"))
      (node (ref "R23W") (pin "1") (pinfunction "1_1") (pintype "passive"))
      (node (ref "TP20W") (pin "1") (pinfunction "1_1") (pintype "passive"))
    )
    (net (code "5") (name "/BT_Ctrl_Vreg") (class "Default")
      (node (ref "P2W") (pin "18") (pinfunction "18_18") (pintype "passive"))
      (node (ref "TP12W") (pin "1") (pinfunction "1_1") (pintype "passive"))
    )
    (net (code "6") (name "/BT_RST") (class "Default")
      (node (ref "P2W") (pin "16") (pinfunction "16_16") (pintype "passive"))
      (node (ref "R2W") (pin "2") (pinfunction "2_2") (pintype "passive"))
      (node (ref "TP21W") (pin "1") (pinfunction "1_1") (pintype "passive"))
      (node (ref "TP2W") (pin "1") (pinfunction "1_1") (pintype "passive"))
    )
    (net (code "7") (name "/BT_SCL") (class "Default")
      (node (ref "P2W") (pin "2") (pinfunction "2_2") (pintype "passive"))
      (node (ref "R15W") (pin "2") (pinfunction "2_2") (pintype "passive"))
      (node (ref "R5W") (pin "1") (pinfunction "1_1") (pintype "passive"))
      (node (ref "TP10W") (pin "1") (pinfunction "1_1") (pintype "passive"))
      (node (ref "TP14W") (pin "1") (pinfunction "1_1") (pintype "passive"))
    )
    (net (code "8") (name "/BT_SDA") (class "Default")
      (node (ref "P2W") (pin "1") (pinfunction "1_1") (pintype "passive"))
      (node (ref "R11W") (pin "2") (pinfunction "2_2") (pintype "passive"))
      (node (ref "R6W") (pin "1") (pinfunction "1_1") (pintype "passive"))
      (node (ref "TP25W") (pin "1") (pinfunction "1_1") (pintype "passive"))
      (node (ref "TP9W") (pin "1") (pinfunction "1_1") (pintype "passive"))
    )
    (net (code "9") (name "/BT_Ver") (class "Default")
      (node (ref "P2W") (pin "24") (pinfunction "24_24") (pintype "passive"))
      (node (ref "R10W") (pin "2") (pinfunction "2_2") (pintype "passive"))
      (node (ref "R13W") (pin "1") (pinfunction "1_1") (pintype "passive"))
      (node (ref "TP7W") (pin "1") (pinfunction "1_1") (pintype "passive"))
    )
    (net (code "10") (name "/BUD_N") (class "Default")
      (node (ref "L2W") (pin "4") (pinfunction "4_4") (pintype "passive"))
      (node (ref "U1W") (pin "28") (pinfunction "DM_28") (pintype "passive"))
    )
    (net (code "11") (name "/BUD_P") (class "Default")
      (node (ref "L2W") (pin "3") (pinfunction "3_3") (pintype "passive"))
      (node (ref "U1W") (pin "27") (pinfunction "DP_27") (pintype "passive"))
    )
    (net (code "12") (name "/FLASH_CS") (class "Default")
      (node (ref "R33W") (pin "2") (pinfunction "2_2") (pintype "passive"))
      (node (ref "R34W") (pin "2") (pinfunction "2_2") (pintype "passive"))
      (node (ref "U2W") (pin "1") (pinfunction "CS#_1") (pintype "passive"))
    )
    (net (code "13") (name "/FLASH_MISO") (class "Default")
      (node (ref "R36W") (pin "2") (pinfunction "2_2") (pintype "passive"))
      (node (ref "U2W") (pin "2") (pinfunction "SO_2") (pintype "passive"))
    )
    (net (code "14") (name "/FLASH_MOSI") (class "Default")
      (node (ref "R37W") (pin "2") (pinfunction "2_2") (pintype "passive"))
      (node (ref "U2W") (pin "5") (pinfunction "SI_5") (pintype "passive"))
    )
    (net (code "15") (name "/FLASH_SCLK") (class "Default")
      (node (ref "R35W") (pin "2") (pinfunction "2_2") (pintype "passive"))
      (node (ref "U2W") (pin "6") (pinfunction "SCLK_6") (pintype "passive"))
    )
    (net (code "16") (name "/GPIO0") (class "Default")
      (node (ref "R5W") (pin "2") (pinfunction "2_2") (pintype "passive"))
      (node (ref "U1W") (pin "59") (pinfunction "GPIO0/PWM1/MCLKTX&RX/I2C_SCL_59") (pintype "passive"))
    )
    (net (code "17") (name "/GPIO1") (class "Default")
      (node (ref "R6W") (pin "2") (pinfunction "2_2") (pintype "passive"))
      (node (ref "U1W") (pin "57") (pinfunction "GPIO1/PWM3/BCLKTX&RX/SPI2_MISO/I2C_SDA_57") (pintype "passive"))
    )
    (net (code "18") (name "/GPIO2{slash}UART_RX") (class "Default")
      (node (ref "P1W") (pin "1") (pinfunction "1_1") (pintype "passive"))
      (node (ref "U1W") (pin "58") (pinfunction "GPIO2/SPI1_MOSI/PWM2/ADC4/LRCLKTX&RX/ORX_58") (pintype "passive"))
    )
    (net (code "19") (name "/GPIO3{slash}UART_TX") (class "Default")
      (node (ref "P1W") (pin "2") (pinfunction "2_2") (pintype "passive"))
      (node (ref "U1W") (pin "56") (pinfunction "GPIO3/SPI1_CLK/0TX/I2SDOUT&DIN_56") (pintype "passive"))
    )
    (net (code "20") (name "/GPIO8") (class "Default")
      (node (ref "R27W") (pin "1") (pinfunction "1_1") (pintype "passive"))
      (node (ref "U1W") (pin "12") (pinfunction "GPIO8/SPI1&2_SS/PWM3/ADC5/SD1_CLK_12") (pintype "passive"))
    )
    (net (code "21") (name "/GPIO9") (class "Default")
      (node (ref "R28W") (pin "1") (pinfunction "1_1") (pintype "passive"))
      (node (ref "R35W") (pin "1") (pinfunction "1_1") (pintype "passive"))
      (node (ref "U1W") (pin "13") (pinfunction "GPIO9/SPI1&2_CLK/PWM1/ADC6/SD1_CMD_13") (pintype "passive"))
    )
    (net (code "22") (name "/GPIO10") (class "Default")
      (node (ref "R30W") (pin "1") (pinfunction "1_1") (pintype "passive"))
      (node (ref "R36W") (pin "1") (pinfunction "1_1") (pintype "passive"))
      (node (ref "U1W") (pin "11") (pinfunction "GPIO10/SPI1&_MISO/ADC7/SD1_DAT0_11") (pintype "passive"))
    )
    (net (code "23") (name "/GPIO11") (class "Default")
      (node (ref "R29W") (pin "1") (pinfunction "1_1") (pintype "passive"))
      (node (ref "R37W") (pin "1") (pinfunction "1_1") (pintype "passive"))
      (node (ref "U1W") (pin "9") (pinfunction "GPIO11/SPI1&2_MOSI/PWM6/ADC8_9") (pintype "passive"))
    )
    (net (code "24") (name "/GPIO13") (class "Default")
      (node (ref "R32W") (pin "1") (pinfunction "1_1") (pintype "passive"))
      (node (ref "U1W") (pin "14") (pinfunction "GPIO13/PWM8/1RTS/SPI1_IO3_14") (pintype "passive"))
    )
    (net (code "25") (name "/GPIO14") (class "Default")
      (node (ref "R31W") (pin "1") (pinfunction "1_1") (pintype "passive"))
      (node (ref "U1W") (pin "15") (pinfunction "GPIO14/ADC11/SPI1_IO2_15") (pintype "passive"))
    )
    (net (code "26") (name "/GPIO16") (class "Default")
      (node (ref "R34W") (pin "1") (pinfunction "1_1") (pintype "passive"))
      (node (ref "U1W") (pin "8") (pinfunction "GPIO16/SPI1&2_SS/PWM4/0RX/SD0_CMD_8") (pintype "passive"))
    )
    (net (code "27") (name "/Line_L_N") (class "Default")
      (node (ref "P2W") (pin "15") (pinfunction "15_15") (pintype "passive"))
      (node (ref "R9W") (pin "2") (pinfunction "2_2") (pintype "passive"))
      (node (ref "TP30W") (pin "1") (pinfunction "1_1") (pintype "passive"))
    )
    (net (code "28") (name "/Line_L_P") (class "Default")
      (node (ref "P2W") (pin "13") (pinfunction "13_13") (pintype "passive"))
      (node (ref "R7W") (pin "2") (pinfunction "2_2") (pintype "passive"))
      (node (ref "TP29W") (pin "1") (pinfunction "1_1") (pintype "passive"))
    )
    (net (code "29") (name "/Line_R_N") (class "Default")
      (node (ref "P2W") (pin "19") (pinfunction "19_19") (pintype "passive"))
      (node (ref "R16W") (pin "2") (pinfunction "2_2") (pintype "passive"))
      (node (ref "TP32W") (pin "1") (pinfunction "1_1") (pintype "passive"))
    )
    (net (code "30") (name "/Line_R_P") (class "Default")
      (node (ref "P2W") (pin "17") (pinfunction "17_17") (pintype "passive"))
      (node (ref "R12W") (pin "2") (pinfunction "2_2") (pintype "passive"))
      (node (ref "TP31W") (pin "1") (pinfunction "1_1") (pintype "passive"))
    )
    (net (code "31") (name "/MCU_RX") (class "Default")
      (node (ref "P2W") (pin "10") (pinfunction "10_10") (pintype "passive"))
      (node (ref "TP18W") (pin "1") (pinfunction "1_1") (pintype "passive"))
      (node (ref "TP5W") (pin "1") (pinfunction "1_1") (pintype "passive"))
      (node (ref "U1W") (pin "20") (pinfunction "GPIO21/PWM0/TPADC/0RX/1TX/MCLKTX&RX/MOSI_20") (pintype "passive"))
    )
    (net (code "32") (name "/MCU_TX") (class "Default")
      (node (ref "P2W") (pin "12") (pinfunction "12_12") (pintype "passive"))
      (node (ref "TP19W") (pin "1") (pinfunction "1_1") (pintype "passive"))
      (node (ref "TP6W") (pin "1") (pinfunction "1_1") (pintype "passive"))
      (node (ref "U1W") (pin "17") (pinfunction "GPIO22/PWM1/0TX/1RX/ADC2/LRCLK_TX&RX/IR_17") (pintype "passive"))
    )
    (net (code "33") (name "/ON{slash}OFF") (class "Default")
      (node (ref "D1W") (pin "K") (pinfunction "K_K") (pintype "passive"))
      (node (ref "R38W") (pin "2") (pinfunction "2_2") (pintype "passive"))
      (node (ref "R39W") (pin "1") (pinfunction "1_1") (pintype "passive"))
      (node (ref "R40W") (pin "1") (pinfunction "1_1") (pintype "passive"))
    )
    (net (code "34") (name "/PSRAM_CE") (class "Default")
      (node (ref "R27W") (pin "2") (pinfunction "2_2") (pintype "passive"))
      (node (ref "U4W") (pin "1") (pinfunction "~{CE}_1") (pintype "passive"))
    )
    (net (code "35") (name "/PSRAM_SCLK") (class "Default")
      (node (ref "R28W") (pin "2") (pinfunction "2_2") (pintype "passive"))
      (node (ref "U4W") (pin "6") (pinfunction "SCLK_6") (pintype "passive"))
    )
    (net (code "36") (name "/PSRAM_SIO0") (class "Default")
      (node (ref "R29W") (pin "2") (pinfunction "2_2") (pintype "passive"))
      (node (ref "U4W") (pin "5") (pinfunction "SI/SIO[0]_5") (pintype "passive"))
    )
    (net (code "37") (name "/PSRAM_SIO1") (class "Default")
      (node (ref "R30W") (pin "2") (pinfunction "2_2") (pintype "passive"))
      (node (ref "U4W") (pin "2") (pinfunction "SO/SIO[1]_2") (pintype "passive"))
    )
    (net (code "38") (name "/PSRAM_SIO2") (class "Default")
      (node (ref "R26W") (pin "2") (pinfunction "2_2") (pintype "passive"))
      (node (ref "R31W") (pin "2") (pinfunction "2_2") (pintype "passive"))
      (node (ref "U4W") (pin "3") (pinfunction "SIO[2]_3") (pintype "passive"))
    )
    (net (code "39") (name "/PSRAM_SIO3") (class "Default")
      (node (ref "R25W") (pin "2") (pinfunction "2_2") (pintype "passive"))
      (node (ref "R32W") (pin "2") (pinfunction "2_2") (pintype "passive"))
      (node (ref "U4W") (pin "7") (pinfunction "SIO[3]_7") (pintype "passive"))
    )
    (net (code "40") (name "/USB_B_N") (class "Default")
      (node (ref "L2W") (pin "2") (pinfunction "2_2") (pintype "passive"))
      (node (ref "P2W") (pin "20") (pinfunction "20_20") (pintype "passive"))
      (node (ref "TP22W") (pin "1") (pinfunction "1_1") (pintype "passive"))
    )
    (net (code "41") (name "/USB_B_P") (class "Default")
      (node (ref "L2W") (pin "1") (pinfunction "1_1") (pintype "passive"))
      (node (ref "P2W") (pin "22") (pinfunction "22_22") (pintype "passive"))
      (node (ref "TP23W") (pin "1") (pinfunction "1_1") (pintype "passive"))
    )
    (net (code "42") (name "3V3_STB") (class "Default")
      (node (ref "P2W") (pin "11") (pinfunction "11_11") (pintype "passive"))
      (node (ref "R10W") (pin "1") (pinfunction "1_1") (pintype "passive"))
      (node (ref "TP28W") (pin "1") (pinfunction "1_1") (pintype "passive"))
    )
    (net (code "43") (name "5V_CCPD") (class "Default")
      (node (ref "C24W") (pin "1") (pinfunction "1_1") (pintype "passive"))
      (node (ref "C25W") (pin "2") (pinfunction "2_2") (pintype "passive"))
      (node (ref "P2W") (pin "23") (pinfunction "23_23") (pintype "passive"))
      (node (ref "R22W") (pin "2") (pinfunction "2_2") (pintype "passive"))
      (node (ref "TP34W") (pin "1") (pinfunction "1_1") (pintype "passive"))
      (node (ref "U3W") (pin "1") (pinfunction "VIN_1") (pintype "passive"))
    )
    (net (code "44") (name "AGND") (class "Default")
      (node (ref "R21W") (pin "2") (pinfunction "2_2") (pintype "passive"))
      (node (ref "U1W") (pin "30") (pinfunction "AGND_30") (pintype "passive"))
      (node (ref "U1W") (pin "43") (pinfunction "AGND1_43") (pintype "passive"))
    )
    (net (code "45") (name "BT_AVCC") (class "Default")
      (node (ref "C16W") (pin "1") (pinfunction "1_1") (pintype "passive"))
      (node (ref "C17W") (pin "2") (pinfunction "2_2") (pintype "passive"))
      (node (ref "U1W") (pin "44") (pinfunction "AVCC_44") (pintype "passive"))
    )
    (net (code "46") (name "BT_RTCVDD") (class "Default")
      (node (ref "C7W") (pin "1") (pinfunction "1_1") (pintype "passive"))
      (node (ref "C8W") (pin "1") (pinfunction "1_1") (pintype "passive"))
      (node (ref "R38W") (pin "1") (pinfunction "1_1") (pintype "passive"))
      (node (ref "U1W") (pin "54") (pinfunction "RTCVDD_54") (pintype "passive"))
    )
    (net (code "47") (name "BT_SVCC") (class "Default")
      (node (ref "C14W") (pin "1") (pinfunction "1_1") (pintype "passive"))
      (node (ref "C15W") (pin "2") (pinfunction "2_2") (pintype "passive"))
      (node (ref "R18W") (pin "1") (pinfunction "1_1") (pintype "passive"))
      (node (ref "U1W") (pin "45") (pinfunction "SVCC_45") (pintype "passive"))
    )
    (net (code "48") (name "BT_VBAT") (class "Default")
      (node (ref "C10W") (pin "2") (pinfunction "2_2") (pintype "passive"))
      (node (ref "C11W") (pin "2") (pinfunction "2_2") (pintype "passive"))
      (node (ref "C28W") (pin "1") (pinfunction "1_1") (pintype "passive"))
      (node (ref "C29W") (pin "2") (pinfunction "2_2") (pintype "passive"))
      (node (ref "FB4W") (pin "2") (pinfunction "2_2") (pintype "passive"))
      (node (ref "TP11W") (pin "1") (pinfunction "1_1") (pintype "passive"))
      (node (ref "U1W") (pin "51") (pinfunction "VBAT_51") (pintype "passive"))
    )
    (net (code "49") (name "BT_VBUS") (class "Default")
      (node (ref "C22W") (pin "1") (pinfunction "1_1") (pintype "passive"))
      (node (ref "C23W") (pin "1") (pinfunction "1_1") (pintype "passive"))
      (node (ref "C30W") (pin "2") (pinfunction "2_2") (pintype "passive"))
      (node (ref "C31W") (pin "2") (pinfunction "2_2") (pintype "passive"))
      (node (ref "FB5W") (pin "2") (pinfunction "2_2") (pintype "passive"))
      (node (ref "TP13W") (pin "1") (pinfunction "1_1") (pintype "passive"))
      (node (ref "U1W") (pin "50") (pinfunction "DC5V_50") (pintype "passive"))
    )
    (net (code "50") (name "BT_VCC") (class "Default")
      (node (ref "C12W") (pin "2") (pinfunction "2_2") (pintype "passive"))
      (node (ref "C18W") (pin "2") (pinfunction "2_2") (pintype "passive"))
      (node (ref "C20W") (pin "1") (pinfunction "1_1") (pintype "passive"))
      (node (ref "C21W") (pin "1") (pinfunction "1_1") (pintype "passive"))
      (node (ref "C4W") (pin "2") (pinfunction "2_2") (pintype "passive"))
      (node (ref "C6W") (pin "2") (pinfunction "2_2") (pintype "passive"))
      (node (ref "R11W") (pin "1") (pinfunction "1_1") (pintype "passive"))
      (node (ref "R15W") (pin "1") (pinfunction "1_1") (pintype "passive"))
      (node (ref "R25W") (pin "1") (pinfunction "1_1") (pintype "passive"))
      (node (ref "R26W") (pin "1") (pinfunction "1_1") (pintype "passive"))
      (node (ref "R33W") (pin "1") (pinfunction "1_1") (pintype "passive"))
      (node (ref "U1W") (pin "49") (pinfunction "VCC_49") (pintype "passive"))
      (node (ref "U2W") (pin "3") (pinfunction "WP#_3") (pintype "passive"))
      (node (ref "U2W") (pin "7") (pinfunction "HOLD#_7") (pintype "passive"))
      (node (ref "U2W") (pin "8") (pinfunction "VCC_8") (pintype "passive"))
      (node (ref "U4W") (pin "8") (pinfunction "VDD_8") (pintype "passive"))
    )
    (net (code "51") (name "GND") (class "Default")
      (node (ref "C10W") (pin "1") (pinfunction "1_1") (pintype "passive"))
      (node (ref "C11W") (pin "1") (pinfunction "1_1") (pintype "passive"))
      (node (ref "C12W") (pin "1") (pinfunction "1_1") (pintype "passive"))
      (node (ref "C14W") (pin "2") (pinfunction "2_2") (pintype "passive"))
      (node (ref "C15W") (pin "1") (pinfunction "1_1") (pintype "passive"))
      (node (ref "C16W") (pin "2") (pinfunction "2_2") (pintype "passive"))
      (node (ref "C17W") (pin "1") (pinfunction "1_1") (pintype "passive"))
      (node (ref "C18W") (pin "1") (pinfunction "1_1") (pintype "passive"))
      (node (ref "C19W") (pin "2") (pinfunction "2_2") (pintype "passive"))
      (node (ref "C1W") (pin "2") (pinfunction "2_2") (pintype "passive"))
      (node (ref "C20W") (pin "2") (pinfunction "2_2") (pintype "passive"))
      (node (ref "C21W") (pin "2") (pinfunction "2_2") (pintype "passive"))
      (node (ref "C22W") (pin "2") (pinfunction "2_2") (pintype "passive"))
      (node (ref "C23W") (pin "2") (pinfunction "2_2") (pintype "passive"))
      (node (ref "C24W") (pin "2") (pinfunction "2_2") (pintype "passive"))
      (node (ref "C25W") (pin "1") (pinfunction "1_1") (pintype "passive"))
      (node (ref "C26W") (pin "2") (pinfunction "2_2") (pintype "passive"))
      (node (ref "C27W") (pin "1") (pinfunction "1_1") (pintype "passive"))
      (node (ref "C28W") (pin "2") (pinfunction "2_2") (pintype "passive"))
      (node (ref "C29W") (pin "1") (pinfunction "1_1") (pintype "passive"))
      (node (ref "C2W") (pin "2") (pinfunction "2_2") (pintype "passive"))
      (node (ref "C30W") (pin "1") (pinfunction "1_1") (pintype "passive"))
      (node (ref "C31W") (pin "1") (pinfunction "1_1") (pintype "passive"))
      (node (ref "C32W") (pin "1") (pinfunction "1_1") (pintype "passive"))
      (node (ref "C33W") (pin "1") (pinfunction "1_1") (pintype "passive"))
      (node (ref "C4W") (pin "1") (pinfunction "1_1") (pintype "passive"))
      (node (ref "C6W") (pin "1") (pinfunction "1_1") (pintype "passive"))
      (node (ref "C7W") (pin "2") (pinfunction "2_2") (pintype "passive"))
      (node (ref "C8W") (pin "2") (pinfunction "2_2") (pintype "passive"))
      (node (ref "J1W") (pin "2") (pinfunction "IN_2") (pintype "passive"))
      (node (ref "MH1W") (pin "1") (pinfunction "1_1") (pintype "passive"))
      (node (ref "MH2W") (pin "1") (pinfunction "1_1") (pintype "passive"))
      (node (ref "MH3W") (pin "1") (pinfunction "1_1") (pintype "passive"))
      (node (ref "MH4W") (pin "1") (pinfunction "1_1") (pintype "passive"))
      (node (ref "P1W") (pin "3") (pinfunction "3_3") (pintype "passive"))
      (node (ref "P2W") (pin "21") (pinfunction "21_21") (pintype "passive"))
      (node (ref "P2W") (pin "3") (pinfunction "3_3") (pintype "passive"))
      (node (ref "P2W") (pin "5") (pinfunction "5_5") (pintype "passive"))
      (node (ref "P2W") (pin "7") (pinfunction "7_7") (pintype "passive"))
      (node (ref "Q4W") (pin "S") (pinfunction "S_S") (pintype "passive"))
      (node (ref "R13W") (pin "2") (pinfunction "2_2") (pintype "passive"))
      (node (ref "R19W") (pin "2") (pinfunction "2_2") (pintype "passive"))
      (node (ref "R21W") (pin "1") (pinfunction "1_1") (pintype "passive"))
      (node (ref "R24W") (pin "2") (pinfunction "2_2") (pintype "passive"))
      (node (ref "R40W") (pin "2") (pinfunction "2_2") (pintype "passive"))
      (node (ref "R41W") (pin "2") (pinfunction "2_2") (pintype "passive"))
      (node (ref "R44W") (pin "1") (pinfunction "1_1") (pintype "passive"))
      (node (ref "TP26W") (pin "1") (pinfunction "1_1") (pintype "passive"))
      (node (ref "TP33W") (pin "1") (pinfunction "1_1") (pintype "passive"))
      (node (ref "U1W") (pin "2") (pinfunction "GND_2") (pintype "passive"))
      (node (ref "U1W") (pin "29") (pinfunction "GND1_29") (pintype "passive"))
      (node (ref "U1W") (pin "52") (pinfunction "GND2_52") (pintype "passive"))
      (node (ref "U2W") (pin "4") (pinfunction "VSS_4") (pintype "passive"))
      (node (ref "U3W") (pin "2") (pinfunction "GND_2") (pintype "passive"))
      (node (ref "U4W") (pin "4") (pinfunction "VSS_4") (pintype "passive"))
    )
    (net (code "52") (name "Net-(C3W-Pad2)") (class "Default")
      (node (ref "C3W") (pin "2") (pinfunction "2_2") (pintype "passive"))
      (node (ref "R14W") (pin "2") (pinfunction "2_2") (pintype "passive"))
      (node (ref "R7W") (pin "1") (pinfunction "1_1") (pintype "passive"))
    )
    (net (code "53") (name "Net-(C5W-Pad2)") (class "Default")
      (node (ref "C5W") (pin "2") (pinfunction "2_2") (pintype "passive"))
      (node (ref "R12W") (pin "1") (pinfunction "1_1") (pintype "passive"))
      (node (ref "R8W") (pin "2") (pinfunction "2_2") (pintype "passive"))
    )
    (net (code "54") (name "Net-(C19W-Pad1)") (class "Default")
      (node (ref "C19W") (pin "1") (pinfunction "1_1") (pintype "passive"))
      (node (ref "Q3W") (pin "S") (pinfunction "S_S") (pintype "passive"))
      (node (ref "R22W") (pin "1") (pinfunction "1_1") (pintype "passive"))
      (node (ref "R45W") (pin "1") (pinfunction "1_1") (pintype "passive"))
    )
    (net (code "55") (name "Net-(C34W-Pad2)") (class "Default")
      (node (ref "C34W") (pin "2") (pinfunction "2_2") (pintype "passive"))
      (node (ref "R14W") (pin "1") (pinfunction "1_1") (pintype "passive"))
      (node (ref "R9W") (pin "1") (pinfunction "1_1") (pintype "passive"))
    )
    (net (code "56") (name "Net-(C35W-Pad2)") (class "Default")
      (node (ref "C35W") (pin "2") (pinfunction "2_2") (pintype "passive"))
      (node (ref "R16W") (pin "1") (pinfunction "1_1") (pintype "passive"))
      (node (ref "R8W") (pin "1") (pinfunction "1_1") (pintype "passive"))
    )
    (net (code "57") (name "Net-(D1W-PadA)") (class "Default")
      (node (ref "D1W") (pin "A") (pinfunction "A_A") (pintype "passive"))
      (node (ref "R2W") (pin "1") (pinfunction "1_1") (pintype "passive"))
      (node (ref "R41W") (pin "1") (pinfunction "1_1") (pintype "passive"))
    )
    (net (code "58") (name "Net-(FB1W-Pad2)") (class "Default")
      (node (ref "FB1W") (pin "2") (pinfunction "2_2") (pintype "passive"))
      (node (ref "R1W") (pin "2") (pinfunction "2_2") (pintype "passive"))
    )
    (net (code "59") (name "Net-(FB2W-Pad2)") (class "Default")
      (node (ref "FB2W") (pin "2") (pinfunction "2_2") (pintype "passive"))
      (node (ref "R3W") (pin "2") (pinfunction "2_2") (pintype "passive"))
    )
    (net (code "60") (name "Net-(FB3W-Pad2)") (class "Default")
      (node (ref "FB3W") (pin "2") (pinfunction "2_2") (pintype "passive"))
      (node (ref "R4W") (pin "2") (pinfunction "2_2") (pintype "passive"))
    )
    (net (code "61") (name "Net-(FB5W-Pad1)") (class "Default")
      (node (ref "FB5W") (pin "1") (pinfunction "1_1") (pintype "passive"))
      (node (ref "Q3W") (pin "D") (pinfunction "D_D") (pintype "passive"))
    )
    (net (code "62") (name "Net-(J1W-OUT)") (class "Default")
      (node (ref "C1W") (pin "1") (pinfunction "1_1") (pintype "passive"))
      (node (ref "J1W") (pin "1") (pinfunction "OUT_1") (pintype "passive"))
      (node (ref "L1W") (pin "1") (pinfunction "1_1") (pintype "passive"))
    )
    (net (code "63") (name "Net-(Q3W-PadG)") (class "Default")
      (node (ref "Q3W") (pin "G") (pinfunction "G_G") (pintype "passive"))
      (node (ref "Q4W") (pin "D") (pinfunction "D_D") (pintype "passive"))
      (node (ref "R45W") (pin "2") (pinfunction "2_2") (pintype "passive"))
    )
    (net (code "64") (name "Net-(Q4W-PadG)") (class "Default")
      (node (ref "Q4W") (pin "G") (pinfunction "G_G") (pintype "passive"))
      (node (ref "R23W") (pin "2") (pinfunction "2_2") (pintype "passive"))
      (node (ref "R24W") (pin "1") (pinfunction "1_1") (pintype "passive"))
    )
    (net (code "65") (name "Net-(R43W-Pad1)") (class "Default")
      (node (ref "R43W") (pin "1") (pinfunction "1_1") (pintype "passive"))
      (node (ref "R44W") (pin "2") (pinfunction "2_2") (pintype "passive"))
    )
    (net (code "66") (name "Net-(U1W-AUX0L{slash}GPIO46)") (class "Default")
      (node (ref "C3W") (pin "1") (pinfunction "1_1") (pintype "passive"))
      (node (ref "U1W") (pin "39") (pinfunction "AUX0L/GPIO46_39") (pintype "passive"))
    )
    (net (code "67") (name "Net-(U1W-AUX0R{slash}GPIO47)") (class "Default")
      (node (ref "C34W") (pin "1") (pinfunction "1_1") (pintype "passive"))
      (node (ref "U1W") (pin "40") (pinfunction "AUX0R/GPIO47_40") (pintype "passive"))
    )
    (net (code "68") (name "Net-(U1W-AUX1L{slash}GPIO48)") (class "Default")
      (node (ref "C5W") (pin "1") (pinfunction "1_1") (pintype "passive"))
      (node (ref "U1W") (pin "41") (pinfunction "AUX1L/GPIO48_41") (pintype "passive"))
    )
    (net (code "69") (name "Net-(U1W-AUX1R{slash}GPIO49)") (class "Default")
      (node (ref "C35W") (pin "1") (pinfunction "1_1") (pintype "passive"))
      (node (ref "U1W") (pin "42") (pinfunction "AUX1R/GPIO49_42") (pintype "passive"))
    )
    (net (code "70") (name "Net-(U1W-GPIO33{slash}BCLK_TX&RX)") (class "Default")
      (node (ref "R1W") (pin "1") (pinfunction "1_1") (pintype "passive"))
      (node (ref "U1W") (pin "6") (pinfunction "GPIO33/BCLK_TX&RX_6") (pintype "passive"))
    )
    (net (code "71") (name "Net-(U1W-GPIO35{slash}SPDIF_TX{slash}I2S_DOUT&DIN)") (class "Default")
      (node (ref "R4W") (pin "1") (pinfunction "1_1") (pintype "passive"))
      (node (ref "U1W") (pin "4") (pinfunction "GPIO35/SPDIF_TX/I2S_DOUT&DIN_4") (pintype "passive"))
    )
    (net (code "72") (name "Net-(U1W-ON{slash}OFF)") (class "Default")
      (node (ref "C32W") (pin "2") (pinfunction "2_2") (pintype "passive"))
      (node (ref "R39W") (pin "2") (pinfunction "2_2") (pintype "passive"))
      (node (ref "U1W") (pin "53") (pinfunction "ON/OFF_53") (pintype "passive"))
    )
    (net (code "73") (name "Net-(U1W-PIO34{slash}LRCLK_TX&RX)") (class "Default")
      (node (ref "R3W") (pin "1") (pinfunction "1_1") (pintype "passive"))
      (node (ref "U1W") (pin "5") (pinfunction "PIO34/LRCLK_TX&RX_5") (pintype "passive"))
    )
    (net (code "74") (name "Net-(U1W-RFIO)") (class "Default")
      (node (ref "C2W") (pin "1") (pinfunction "1_1") (pintype "passive"))
      (node (ref "L1W") (pin "2") (pinfunction "2_2") (pintype "passive"))
      (node (ref "U1W") (pin "1") (pinfunction "RFIO_1") (pintype "passive"))
    )
    (net (code "75") (name "Net-(U1W-WIO0{slash}ADC1)") (class "Default")
      (node (ref "C33W") (pin "2") (pinfunction "2_2") (pintype "passive"))
      (node (ref "R18W") (pin "2") (pinfunction "2_2") (pintype "passive"))
      (node (ref "U1W") (pin "46") (pinfunction "WIO0/ADC1_46") (pintype "passive"))
    )
    (net (code "76") (name "Net-(U3W-BP{slash}FB)") (class "Default")
      (node (ref "R42W") (pin "2") (pinfunction "2_2") (pintype "passive"))
      (node (ref "R43W") (pin "2") (pinfunction "2_2") (pintype "passive"))
      (node (ref "U3W") (pin "4") (pinfunction "BP/FB_4") (pintype "passive"))
    )
    (net (code "77") (name "Net-(U3W-EN)") (class "Default")
      (node (ref "R19W") (pin "1") (pinfunction "1_1") (pintype "passive"))
      (node (ref "R20W") (pin "1") (pinfunction "1_1") (pintype "passive"))
      (node (ref "U3W") (pin "3") (pinfunction "EN_3") (pintype "passive"))
    )
    (net (code "78") (name "Net-(U3W-VOUT)") (class "Default")
      (node (ref "C26W") (pin "1") (pinfunction "1_1") (pintype "passive"))
      (node (ref "C27W") (pin "2") (pinfunction "2_2") (pintype "passive"))
      (node (ref "FB4W") (pin "1") (pinfunction "1_1") (pintype "passive"))
      (node (ref "R42W") (pin "1") (pinfunction "1_1") (pintype "passive"))
      (node (ref "U3W") (pin "5") (pinfunction "VOUT_5") (pintype "passive"))
    )
    (net (code "79") (name "VSys") (class "Default")
      (node (ref "P2W") (pin "9") (pinfunction "9_9") (pintype "passive"))
      (node (ref "TP27W") (pin "1") (pinfunction "1_1") (pintype "passive"))
    )
    (net (code "80") (name "unconnected-(MK1W-PadMK_B)") (class "Default")
      (node (ref "MK1W") (pin "MK_B") (pinfunction "MK_B_MK_B") (pintype "passive"))
    )
    (net (code "81") (name "unconnected-(MK1W-PadMK_T)") (class "Default")
      (node (ref "MK1W") (pin "MK_T") (pinfunction "MK_T_MK_T") (pintype "passive"))
    )
    (net (code "82") (name "unconnected-(MK2W-PadMK_B)") (class "Default")
      (node (ref "MK2W") (pin "MK_B") (pinfunction "MK_B_MK_B") (pintype "passive"))
    )
    (net (code "83") (name "unconnected-(MK2W-PadMK_T)") (class "Default")
      (node (ref "MK2W") (pin "MK_T") (pinfunction "MK_T_MK_T") (pintype "passive"))
    )
    (net (code "84") (name "unconnected-(U1W-AOUTL{slash}GPIO50-Pad33)") (class "Default")
      (node (ref "U1W") (pin "33") (pinfunction "AOUTL/GPIO50_33") (pintype "passive+no_connect"))
    )
    (net (code "85") (name "unconnected-(U1W-AOUTR{slash}GPIO52-Pad32)") (class "Default")
      (node (ref "U1W") (pin "32") (pinfunction "AOUTR/GPIO52_32") (pintype "passive+no_connect"))
    )
    (net (code "86") (name "unconnected-(U1W-AUX2L{slash}GPIO54-Pad37)") (class "Default")
      (node (ref "U1W") (pin "37") (pinfunction "AUX2L/GPIO54_37") (pintype "passive"))
    )
    (net (code "87") (name "unconnected-(U1W-AUX2R{slash}GPIO55-Pad38)") (class "Default")
      (node (ref "U1W") (pin "38") (pinfunction "AUX2R/GPIO55_38") (pintype "passive"))
    )
    (net (code "88") (name "unconnected-(U1W-GPIO4{slash}PWM1{slash}IR-Pad47)") (class "Default")
      (node (ref "U1W") (pin "47") (pinfunction "GPIO4/PWM1/IR_47") (pintype "passive"))
    )
    (net (code "89") (name "unconnected-(U1W-GPIO5{slash}PWM3-Pad21)") (class "Default")
      (node (ref "U1W") (pin "21") (pinfunction "GPIO5/PWM3_21") (pintype "passive"))
    )
    (net (code "90") (name "unconnected-(U1W-GPIO6{slash}PWM4{slash}LRCLK_TX&RX-Pad19)") (class "Default")
      (node (ref "U1W") (pin "19") (pinfunction "GPIO6/PWM4/LRCLK_TX&RX_19") (pintype "passive"))
    )
    (net (code "91") (name "unconnected-(U1W-GPIO7{slash}PWM0{slash}1TX{slash}FMCLK{slash}I2SDOUT&DIN{slash}SPDIFRX-Pad48)") (class "Default")
      (node (ref "U1W") (pin "48") (pinfunction "GPIO7/PWM0/1TX/FMCLK/I2SDOUT&DIN/SPDIFRX_48") (pintype "passive"))
    )
    (net (code "92") (name "unconnected-(U1W-GPIO12{slash}PWM7{slash}ADC9{slash}SD1_DAT2-Pad10)") (class "Default")
      (node (ref "U1W") (pin "10") (pinfunction "GPIO12/PWM7/ADC9/SD1_DAT2_10") (pintype "passive"))
    )
    (net (code "93") (name "unconnected-(U1W-GPIO15{slash}PWM4{slash}1RX{slash}SPI1_IO3{slash}MCLK_TX&RX-Pad16)") (class "Default")
      (node (ref "U1W") (pin "16") (pinfunction "GPIO15/PWM4/1RX/SPI1_IO3/MCLK_TX&RX_16") (pintype "passive"))
    )
    (net (code "94") (name "unconnected-(U1W-GPIO17{slash}OTX{slash}SPI1&2_CLK{slash}SD0_CLK0-Pad26)") (class "Default")
      (node (ref "U1W") (pin "26") (pinfunction "GPIO17/OTX/SPI1&2_CLK/SD0_CLK0_26") (pintype "passive"))
    )
    (net (code "95") (name "unconnected-(U1W-GPIO19{slash}I2C_SDA-Pad55)") (class "Default")
      (node (ref "U1W") (pin "55") (pinfunction "GPIO19/I2C_SDA_55") (pintype "passive"))
    )
    (net (code "96") (name "unconnected-(U1W-GPIO20{slash}PWM2{slash}SPI1&SPI2_MISO-Pad25)") (class "Default")
      (node (ref "U1W") (pin "25") (pinfunction "GPIO20/PWM2/SPI1&SPI2_MISO_25") (pintype "passive"))
    )
    (net (code "97") (name "unconnected-(U1W-GPIO23{slash}PWM2{slash}0TX{slash}ADC3{slash}BCLKTX&RX{slash}SPDIF_TX-Pad18)") (class "Default")
      (node (ref "U1W") (pin "18") (pinfunction "GPIO23/PWM2/0TX/ADC3/BCLKTX&RX/SPDIF_TX_18") (pintype "passive"))
    )
    (net (code "98") (name "unconnected-(U1W-GPIO32{slash}MCLK_TX&RX-Pad7)") (class "Default")
      (node (ref "U1W") (pin "7") (pinfunction "GPIO32/MCLK_TX&RX_7") (pintype "passive+no_connect"))
    )
    (net (code "99") (name "unconnected-(U1W-GPIO38{slash}PWM0{slash}I2SDOUT&DIN{slash}SPDIFRX-Pad24)") (class "Default")
      (node (ref "U1W") (pin "24") (pinfunction "GPIO38/PWM0/I2SDOUT&DIN/SPDIFRX_24") (pintype "passive"))
    )
    (net (code "100") (name "unconnected-(U1W-GPIO39{slash}PWM1{slash}BCLK_TX&RX-Pad23)") (class "Default")
      (node (ref "U1W") (pin "23") (pinfunction "GPIO39/PWM1/BCLK_TX&RX_23") (pintype "passive"))
    )
    (net (code "101") (name "unconnected-(U1W-GPIO40{slash}PWM2{slash}MCLK_TX&RX-Pad22)") (class "Default")
      (node (ref "U1W") (pin "22") (pinfunction "GPIO40/PWM2/MCLK_TX&RX_22") (pintype "passive"))
    )
    (net (code "102") (name "unconnected-(U1W-GPIO42{slash}PWM3&5{slash}BCLK_TX&RX{slash}IR{slash}1TX-Pad3)") (class "Default")
      (node (ref "U1W") (pin "3") (pinfunction "GPIO42/PWM3&5/BCLK_TX&RX/IR/1TX_3") (pintype "passive"))
    )
    (net (code "103") (name "unconnected-(U1W-MIC_INL{slash}GPIO44{slash}DMIC_CLK-Pad35)") (class "Default")
      (node (ref "U1W") (pin "35") (pinfunction "MIC_INL/GPIO44/DMIC_CLK_35") (pintype "passive"))
    )
    (net (code "104") (name "unconnected-(U1W-MIC_INR{slash}GPIO45{slash}DMIC_DTA-Pad36)") (class "Default")
      (node (ref "U1W") (pin "36") (pinfunction "MIC_INR/GPIO45/DMIC_DTA_36") (pintype "passive"))
    )
    (net (code "105") (name "unconnected-(U1W-VRO_S{slash}GPIO53{slash}I2SDOUT&DIN{slash}PWM5-Pad31)") (class "Default")
      (node (ref "U1W") (pin "31") (pinfunction "VRO_S/GPIO53/I2SDOUT&DIN/PWM5_31") (pintype "passive+no_connect"))
    )
    (net (code "106") (name "unconnected-(U1W-VRO{slash}GPIO51{slash}LRCLK_TX&RX{slash}PWM3-Pad34)") (class "Default")
      (node (ref "U1W") (pin "34") (pinfunction "VRO/GPIO51/LRCLK_TX&RX/PWM3_34") (pintype "passive+no_connect"))
    )
  )
)
